# Sheet1.net
KiCad netlist of a schematic drawn in Altium Designer
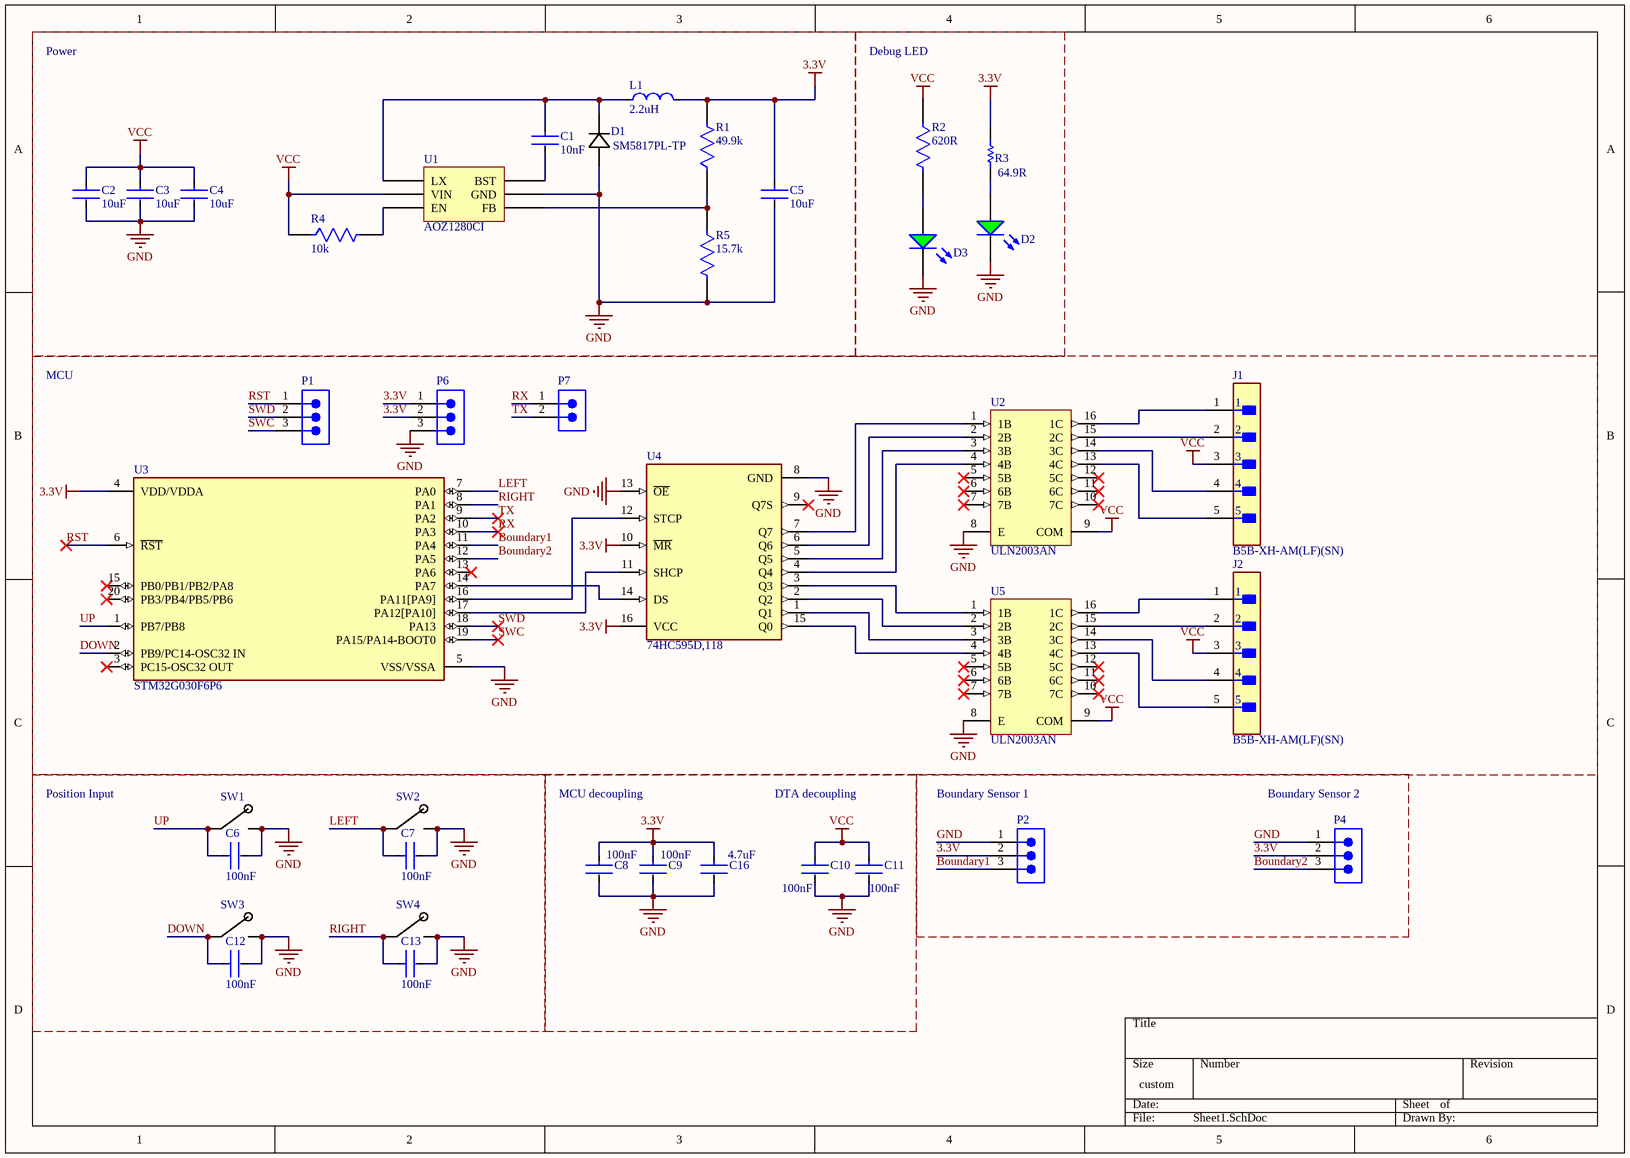
[diagram p0: Sheet1.SchDoc]

(export (version "E")
  (design (tool "Eeschema 10.0.6"))
  (components
    (comp (ref "C1")
      (value "10nF")
      (footprint "FP-CC0603-DA-MFG")
      (description "CAP CER 10000PF 50V X7R 0603")
      (fields (field (name "TOLERANCE") "0.1") (field (name "MANUFACTURER PART NUMBER") "CC0603KRX7R9BB103"))
      (libsource (lib "Altium Content Vault") (part "11868f565c42a9108669ba33697ecf6"))
    )
    (comp (ref "C2")
      (value "10uF")
      (footprint "FP-CL31-IPC_C")
      (description "CAP CER 10UF 50V X5R 1206")
      (fields (field (name "TOLERANCE") "10%") (field (name "MANUFACTURER") "Samsung"))
      (libsource (lib "Altium Content Vault") (part "11868f565c42a9108669ba33697ecf6"))
    )
    (comp (ref "C3")
      (value "10uF")
      (footprint "FP-CL31-IPC_C")
      (description "CAP CER 10UF 50V X5R 1206")
      (fields (field (name "TOLERANCE") "10%") (field (name "MANUFACTURER") "Samsung"))
      (libsource (lib "Altium Content Vault") (part "11868f565c42a9108669ba33697ecf6"))
    )
    (comp (ref "C4")
      (value "10uF")
      (footprint "FP-CL31-IPC_C")
      (description "CAP CER 10UF 50V X5R 1206")
      (fields (field (name "TOLERANCE") "10%") (field (name "MANUFACTURER") "Samsung"))
      (libsource (lib "Altium Content Vault") (part "11868f565c42a9108669ba33697ecf6"))
    )
    (comp (ref "C5")
      (value "10uF")
      (footprint "FP-CL10-IPC_C")
      (description "Cap Ceramic 10uF 6.3V X5R ±20% Pad SMD 0603 +85°C T/R")
      (fields (field (name "VOLTAGE") "6.3V") (field (name "TOLERANCE") "20%"))
      (libsource (lib "Altium Content Vault") (part "b4654b650e69147ec39a6b967a45e02"))
    )
    (comp (ref "C6")
      (value "100nF")
      (footprint "FP-CL10-0_1-MFG")
      (description "CAP CER 0.1UF 50V X7R 0603")
      (fields
        (field (name "MANUFACTURER") "Samsung Electro-Mechanics America, Inc")
        (field (name "MANUFACTURER PART NUMBER") "CL10B104JB8NNNC")
      )
      (libsource (lib "Altium Content Vault") (part "b4654b650e69147ec39a6b967a45e02"))
    )
    (comp (ref "C7")
      (value "100nF")
      (footprint "FP-CL10-0_1-MFG")
      (description "CAP CER 0.1UF 50V X7R 0603")
      (fields
        (field (name "MANUFACTURER") "Samsung Electro-Mechanics America, Inc")
        (field (name "MANUFACTURER PART NUMBER") "CL10B104JB8NNNC")
      )
      (libsource (lib "Altium Content Vault") (part "b4654b650e69147ec39a6b967a45e02"))
    )
    (comp (ref "C8")
      (value "100nF")
      (footprint "FP-CL10-0_1-MFG")
      (description "CAP CER 0.1UF 50V X7R 0603")
      (fields
        (field (name "MANUFACTURER") "Samsung Electro-Mechanics America, Inc")
        (field (name "MANUFACTURER PART NUMBER") "CL10B104JB8NNNC")
      )
      (libsource (lib "Altium Content Vault") (part "b4654b650e69147ec39a6b967a45e02"))
    )
    (comp (ref "C9")
      (value "100nF")
      (footprint "FP-CL10-0_1-MFG")
      (description "CAP CER 0.1UF 50V X7R 0603")
      (fields
        (field (name "MANUFACTURER") "Samsung Electro-Mechanics America, Inc")
        (field (name "MANUFACTURER PART NUMBER") "CL10B104JB8NNNC")
      )
      (libsource (lib "Altium Content Vault") (part "b4654b650e69147ec39a6b967a45e02"))
    )
    (comp (ref "C10")
      (value "100nF")
      (footprint "FP-CL10-0_1-MFG")
      (description "CAP CER 0.1UF 50V X7R 0603")
      (fields
        (field (name "MANUFACTURER") "Samsung Electro-Mechanics America, Inc")
        (field (name "MANUFACTURER PART NUMBER") "CL10B104JB8NNNC")
      )
      (libsource (lib "Altium Content Vault") (part "b4654b650e69147ec39a6b967a45e02"))
    )
    (comp (ref "C11")
      (value "100nF")
      (footprint "FP-CL10-0_1-MFG")
      (description "CAP CER 0.1UF 50V X7R 0603")
      (fields
        (field (name "MANUFACTURER") "Samsung Electro-Mechanics America, Inc")
        (field (name "MANUFACTURER PART NUMBER") "CL10B104JB8NNNC")
      )
      (libsource (lib "Altium Content Vault") (part "b4654b650e69147ec39a6b967a45e02"))
    )
    (comp (ref "C12")
      (value "100nF")
      (footprint "FP-CL10-0_1-MFG")
      (description "CAP CER 0.1UF 50V X7R 0603")
      (fields
        (field (name "MANUFACTURER") "Samsung Electro-Mechanics America, Inc")
        (field (name "MANUFACTURER PART NUMBER") "CL10B104JB8NNNC")
      )
      (libsource (lib "Altium Content Vault") (part "b4654b650e69147ec39a6b967a45e02"))
    )
    (comp (ref "C13")
      (value "100nF")
      (footprint "FP-CL10-0_1-MFG")
      (description "CAP CER 0.1UF 50V X7R 0603")
      (fields
        (field (name "MANUFACTURER") "Samsung Electro-Mechanics America, Inc")
        (field (name "MANUFACTURER PART NUMBER") "CL10B104JB8NNNC")
      )
      (libsource (lib "Altium Content Vault") (part "b4654b650e69147ec39a6b967a45e02"))
    )
    (comp (ref "C16")
      (value "CL10A475KP8NNNC")
      (footprint "FP-CL10-IPC_C")
      (description "Cap Ceramic 4.7uF 10V X5R ±10% Pad SMD 0603 +85°C T/R")
      (fields (field (name "CAPACITANCE") "4.7uF") (field (name "TOLERANCE") "10%"))
      (libsource (lib "Altium Content Vault") (part "b4654b650e69147ec39a6b967a45e02"))
    )
    (comp (ref "D1")
      (value "SM5817PL-TP")
      (footprint "SM5817PL-TP-Footprint-1")
      (description "DIODE SCHOTTKY 20V 1A SOD123FL")
      (libsource (lib "Bento") (part "SM5817PL-TP-Symbol-1"))
    )
    (comp (ref "D2")
      (value "150060VS75000")
      (footprint "WL-SMCW_0603_150060xx75000")
      (libsource (lib "Altium Content Vault") (part "LED_Green_2A-1K"))
    )
    (comp (ref "D3")
      (value "150060VS75000")
      (footprint "WL-SMCW_0603_150060xx75000")
      (libsource (lib "Altium Content Vault") (part "LED_Green_2A-1K"))
    )
    (comp (ref "J1")
      (value "B5B-XH-AM(LF)(SN)")
      (footprint "FP-B5B-XH-AM_LF_SN-MFG")
      (description "CONN HEADER VERT 5POS 2.5MM")
      (libsource (lib "Altium Content Vault") (part "bf93c07fd2649a848d0ec8585582aab"))
    )
    (comp (ref "J2")
      (value "B5B-XH-AM(LF)(SN)")
      (footprint "FP-B5B-XH-AM_LF_SN-MFG")
      (description "CONN HEADER VERT 5POS 2.5MM")
      (libsource (lib "Altium Content Vault") (part "bf93c07fd2649a848d0ec8585582aab"))
    )
    (comp (ref "L1")
      (value "2.2uH")
      (footprint "FP-LQM2MPN_G0-MFG")
      (description "Multilayer Type Inductor for Power Lines, 0806 (2016), 2.2μH, 30%, 0.138Ω, 1.2A")
      (fields (field (name "TOLERANCE") "30%"))
      (libsource (lib "Altium Content Vault") (part "725321dda6339637d4d059423bc1c3c"))
    )
    (comp (ref "P1")
      (value "61300311121")
      (footprint "61300311121")
      (libsource (lib "Altium Content Vault") (part "Header_Male_1R_03P"))
    )
    (comp (ref "P2")
      (value "61300311121")
      (footprint "61300311121")
      (libsource (lib "Altium Content Vault") (part "Header_Male_1R_03P"))
    )
    (comp (ref "P4")
      (value "61300311121")
      (footprint "61300311121")
      (libsource (lib "Altium Content Vault") (part "Header_Male_1R_03P"))
    )
    (comp (ref "P6")
      (value "61300311121")
      (footprint "61300311121")
      (libsource (lib "Altium Content Vault") (part "Header_Male_1R_03P"))
    )
    (comp (ref "P7")
      (value "61300211121")
      (footprint "61300211121")
      (libsource (lib "Altium Content Vault") (part "Header_Male_1R_02P"))
    )
    (comp (ref "R1")
      (value "49.9k")
      (footprint "FP-ERJ3EK-IPC_A")
      (description "RES SMD 49.9K OHM 1% 1/10W 0603")
      (fields (field (name "TOLERANCE") "1%"))
      (libsource (lib "Altium Content Vault") (part "1029c3af85768c4190bb7ad29bc67b5"))
    )
    (comp (ref "R2")
      (value "RMCF0603JT620R")
      (footprint "FP-RMCF0603-MFG")
      (description "620Ω ±5% 0.1W 0603 Thick Film Chip Resistor AEC-Q200 compliant")
      (fields (field (name "RESISTANCE") "620R") (field (name "TOLERANCE") "5%"))
      (libsource (lib "Altium Content Vault") (part "1029c3af85768c4190bb7ad29bc67b5"))
    )
    (comp (ref "R3")
      (value "64.9R")
      (footprint "RESC1608X55X25ML10T15")
      (description "RES 64.9 OHM 1% 1/10W 0603")
      (fields (field (name "MANUFACTURER") "Yageo") (field (name "PART NUMBER") "RC0603FR-0764R9L"))
      (libsource (lib "Altium Content Vault") (part "RES"))
    )
    (comp (ref "R4")
      (value "10k")
      (footprint "FP-RMCF0603-IPC_C")
      (description "10kΩ ±5% 0.1W 0603 Thick Film Chip Resistor AEC-Q200 compliant")
      (fields (field (name "TOLERANCE") "5%"))
      (libsource (lib "Altium Content Vault") (part "1029c3af85768c4190bb7ad29bc67b5"))
    )
    (comp (ref "R5")
      (value "15.7k")
      (footprint "FP-RT0603-MFG")
      (description "RES SMD 15.8K OHM 0.1% 1/10W")
      (fields
        (field (name "OCTOPART") "https://octopart.com/rt0603brd0715k8l-yageo-1418310")
        (field (name "TOLERANCE") "0.001")
      )
      (libsource (lib "Altium Content Vault") (part "1029c3af85768c4190bb7ad29bc67b5"))
    )
    (comp (ref "SW1")
      (value "PTS636 SM43 SMTR LFS")
      (footprint "PTS636 SM43 SMTR LFS-Footprint-1")
      (description "SWITCH TACTILE SPST-NO 0.05A 12V")
      (libsource (lib "Bento") (part "PTS636 SM43 SMTR LFS-Symbol-1"))
    )
    (comp (ref "SW2")
      (value "PTS636 SM43 SMTR LFS")
      (footprint "PTS636 SM43 SMTR LFS-Footprint-1")
      (description "SWITCH TACTILE SPST-NO 0.05A 12V")
      (libsource (lib "Bento") (part "PTS636 SM43 SMTR LFS-Symbol-1"))
    )
    (comp (ref "SW3")
      (value "PTS636 SM43 SMTR LFS")
      (footprint "PTS636 SM43 SMTR LFS-Footprint-1")
      (description "SWITCH TACTILE SPST-NO 0.05A 12V")
      (libsource (lib "Bento") (part "PTS636 SM43 SMTR LFS-Symbol-1"))
    )
    (comp (ref "SW4")
      (value "PTS636 SM43 SMTR LFS")
      (footprint "PTS636 SM43 SMTR LFS-Footprint-1")
      (description "SWITCH TACTILE SPST-NO 0.05A 12V")
      (libsource (lib "Bento") (part "PTS636 SM43 SMTR LFS-Symbol-1"))
    )
    (comp (ref "U1")
      (value "AOZ1280CI")
      (footprint "SOT95P280X125-6N")
      (description "Buck Switching Regulator IC Positive Adjustable 0.8V 1 Output 1.2A SOT-23-6")
      (libsource (lib "Bento") (part "AOZ1280CI-Symbol-1"))
    )
    (comp (ref "U2")
      (value "ULN2003AN")
      (footprint "N0016A")
      (fields (field (name "MANUFACTURER") "TexasInstruments"))
      (libsource (lib "Altium Content Vault") (part "TI-ULN2003A-PDIP_N-16"))
    )
    (comp (ref "U3")
      (value "STM32G030F6P6")
      (footprint "FP-TSSOP20-YA-MFG")
      (description "ARM MICROCONTROLLERS - MCU")
      (fields
        (field (name "MANUFACTURER") "STMicroelectronics")
        (field (name "OCTOPART") "https://octopart.com/stm32g030f6p6-stmicroelectronics-103773023")
      )
      (libsource (lib "Altium Content Vault") (part "de2f7cf56ecdc1f1ec6ab3e49dbf5e6"))
    )
    (comp (ref "U4")
      (value "74HC595D,118")
      (footprint "FP-SOT109-1-IPC_C")
      (description "IC SHIFT REGISTER 8BIT 16SOIC")
      (libsource (lib "Altium Content Vault") (part "7b153f231cfcc3ac06dee253bd56617"))
    )
    (comp (ref "U5")
      (value "ULN2003AN")
      (footprint "N0016A")
      (fields (field (name "MANUFACTURER") "TexasInstruments"))
      (libsource (lib "Altium Content Vault") (part "TI-ULN2003A-PDIP_N-16"))
    )
  )
  (nets
    (net (code "1") (name "/Boundary1") (class "Default")
      (node (ref "P2") (pin "3") (pinfunction "3_3") (pintype "passive"))
      (node (ref "U3") (pin "11") (pinfunction "PA4_11") (pintype "bidirectional"))
    )
    (net (code "2") (name "/Boundary2") (class "Default")
      (node (ref "P4") (pin "3") (pinfunction "3_3") (pintype "passive"))
      (node (ref "U3") (pin "12") (pinfunction "PA5_12") (pintype "bidirectional"))
    )
    (net (code "3") (name "/DOWN") (class "Default")
      (node (ref "C12") (pin "1") (pinfunction "1_1") (pintype "passive"))
      (node (ref "SW3") (pin "1") (pinfunction "1_1") (pintype "passive"))
      (node (ref "U3") (pin "2") (pinfunction "PB9/PC14-OSC32_IN_2") (pintype "bidirectional"))
    )
    (net (code "4") (name "/LEFT") (class "Default")
      (node (ref "C7") (pin "1") (pinfunction "1_1") (pintype "passive"))
      (node (ref "SW2") (pin "1") (pinfunction "1_1") (pintype "passive"))
      (node (ref "U3") (pin "7") (pinfunction "PA0_7") (pintype "bidirectional"))
    )
    (net (code "5") (name "/RIGHT") (class "Default")
      (node (ref "C13") (pin "1") (pinfunction "1_1") (pintype "passive"))
      (node (ref "SW4") (pin "1") (pinfunction "1_1") (pintype "passive"))
      (node (ref "U3") (pin "8") (pinfunction "PA1_8") (pintype "bidirectional"))
    )
    (net (code "6") (name "/RST") (class "Default")
      (node (ref "P1") (pin "1") (pinfunction "1_1") (pintype "passive"))
      (node (ref "U3") (pin "6") (pinfunction "~{RST}_6") (pintype "input"))
    )
    (net (code "7") (name "/RX") (class "Default")
      (node (ref "P7") (pin "1") (pinfunction "1_1") (pintype "passive"))
      (node (ref "U3") (pin "10") (pinfunction "PA3_10") (pintype "bidirectional"))
    )
    (net (code "8") (name "/SWC") (class "Default")
      (node (ref "P1") (pin "3") (pinfunction "3_3") (pintype "passive"))
      (node (ref "U3") (pin "19") (pinfunction "PA15/PA14-BOOT0_19") (pintype "bidirectional"))
    )
    (net (code "9") (name "/SWD") (class "Default")
      (node (ref "P1") (pin "2") (pinfunction "2_2") (pintype "passive"))
      (node (ref "U3") (pin "18") (pinfunction "PA13_18") (pintype "bidirectional"))
    )
    (net (code "10") (name "/TX") (class "Default")
      (node (ref "P7") (pin "2") (pinfunction "2_2") (pintype "passive"))
      (node (ref "U3") (pin "9") (pinfunction "PA2_9") (pintype "bidirectional"))
    )
    (net (code "11") (name "/UP") (class "Default")
      (node (ref "C6") (pin "1") (pinfunction "1_1") (pintype "passive"))
      (node (ref "SW1") (pin "1") (pinfunction "1_1") (pintype "passive"))
      (node (ref "U3") (pin "1") (pinfunction "PB7/PB8_1") (pintype "bidirectional"))
    )
    (net (code "12") (name "3.3V") (class "Default")
      (node (ref "C16") (pin "1") (pinfunction "1_1") (pintype "passive"))
      (node (ref "C5") (pin "1") (pinfunction "1_1") (pintype "passive"))
      (node (ref "C8") (pin "1") (pinfunction "1_1") (pintype "passive"))
      (node (ref "C9") (pin "1") (pinfunction "1_1") (pintype "passive"))
      (node (ref "L1") (pin "2") (pinfunction "2_2") (pintype "passive"))
      (node (ref "P2") (pin "2") (pinfunction "2_2") (pintype "passive"))
      (node (ref "P4") (pin "2") (pinfunction "2_2") (pintype "passive"))
      (node (ref "P6") (pin "1") (pinfunction "1_1") (pintype "passive"))
      (node (ref "P6") (pin "2") (pinfunction "2_2") (pintype "passive"))
      (node (ref "R1") (pin "2") (pinfunction "2_2") (pintype "passive"))
      (node (ref "R3") (pin "2") (pinfunction "2_2") (pintype "passive"))
      (node (ref "U3") (pin "4") (pinfunction "VDD/VDDA_4") (pintype "power_in"))
      (node (ref "U4") (pin "10") (pinfunction "~{MR}_10") (pintype "input"))
      (node (ref "U4") (pin "16") (pinfunction "VCC_16") (pintype "power_in"))
    )
    (net (code "13") (name "GND") (class "Default")
      (node (ref "C10") (pin "2") (pinfunction "2_2") (pintype "passive"))
      (node (ref "C11") (pin "2") (pinfunction "2_2") (pintype "passive"))
      (node (ref "C12") (pin "2") (pinfunction "2_2") (pintype "passive"))
      (node (ref "C13") (pin "2") (pinfunction "2_2") (pintype "passive"))
      (node (ref "C16") (pin "2") (pinfunction "2_2") (pintype "passive"))
      (node (ref "C2") (pin "2") (pinfunction "2_2") (pintype "passive"))
      (node (ref "C3") (pin "2") (pinfunction "2_2") (pintype "passive"))
      (node (ref "C4") (pin "2") (pinfunction "2_2") (pintype "passive"))
      (node (ref "C5") (pin "2") (pinfunction "2_2") (pintype "passive"))
      (node (ref "C6") (pin "2") (pinfunction "2_2") (pintype "passive"))
      (node (ref "C7") (pin "2") (pinfunction "2_2") (pintype "passive"))
      (node (ref "C8") (pin "2") (pinfunction "2_2") (pintype "passive"))
      (node (ref "C9") (pin "2") (pinfunction "2_2") (pintype "passive"))
      (node (ref "D1") (pin "2") (pinfunction "2_2") (pintype "passive"))
      (node (ref "D2") (pin "1") (pinfunction "K_1") (pintype "passive"))
      (node (ref "D3") (pin "1") (pinfunction "K_1") (pintype "passive"))
      (node (ref "P2") (pin "1") (pinfunction "1_1") (pintype "passive"))
      (node (ref "P4") (pin "1") (pinfunction "1_1") (pintype "passive"))
      (node (ref "P6") (pin "3") (pinfunction "3_3") (pintype "passive"))
      (node (ref "R5") (pin "2") (pinfunction "2_2") (pintype "passive"))
      (node (ref "SW1") (pin "2") (pinfunction "2_2") (pintype "passive"))
      (node (ref "SW2") (pin "2") (pinfunction "2_2") (pintype "passive"))
      (node (ref "SW3") (pin "2") (pinfunction "2_2") (pintype "passive"))
      (node (ref "SW4") (pin "2") (pinfunction "2_2") (pintype "passive"))
      (node (ref "U1") (pin "2") (pinfunction "GND_2") (pintype "passive"))
      (node (ref "U2") (pin "8") (pinfunction "E_8") (pintype "passive"))
      (node (ref "U3") (pin "5") (pinfunction "VSS/VSSA_5") (pintype "power_in"))
      (node (ref "U4") (pin "13") (pinfunction "~{OE}_13") (pintype "input"))
      (node (ref "U4") (pin "8") (pinfunction "GND_8") (pintype "power_in"))
      (node (ref "U5") (pin "8") (pinfunction "E_8") (pintype "passive"))
    )
    (net (code "14") (name "Net-(D2-A)") (class "Default")
      (node (ref "D2") (pin "2") (pinfunction "A_2") (pintype "passive"))
      (node (ref "R3") (pin "1") (pinfunction "1_1") (pintype "passive"))
    )
    (net (code "15") (name "Net-(D3-A)") (class "Default")
      (node (ref "D3") (pin "2") (pinfunction "A_2") (pintype "passive"))
      (node (ref "R2") (pin "2") (pinfunction "2_2") (pintype "passive"))
    )
    (net (code "16") (name "Net-(U1-BST)") (class "Default")
      (node (ref "C1") (pin "2") (pinfunction "2_2") (pintype "passive"))
      (node (ref "U1") (pin "1") (pinfunction "BST_1") (pintype "passive"))
    )
    (net (code "17") (name "Net-(U1-EN)") (class "Default")
      (node (ref "R4") (pin "2") (pinfunction "2_2") (pintype "passive"))
      (node (ref "U1") (pin "4") (pinfunction "EN_4") (pintype "passive"))
    )
    (net (code "18") (name "Net-(U1-FB)") (class "Default")
      (node (ref "R1") (pin "1") (pinfunction "1_1") (pintype "passive"))
      (node (ref "R5") (pin "1") (pinfunction "1_1") (pintype "passive"))
      (node (ref "U1") (pin "3") (pinfunction "FB_3") (pintype "passive"))
    )
    (net (code "19") (name "Net-(U1-LX)") (class "Default")
      (node (ref "C1") (pin "1") (pinfunction "1_1") (pintype "passive"))
      (node (ref "D1") (pin "1") (pinfunction "1_1") (pintype "passive"))
      (node (ref "L1") (pin "1") (pinfunction "1_1") (pintype "passive"))
      (node (ref "U1") (pin "6") (pinfunction "LX_6") (pintype "passive"))
    )
    (net (code "20") (name "Net-(U2-1B)") (class "Default")
      (node (ref "U2") (pin "1") (pinfunction "1B_1") (pintype "input"))
      (node (ref "U4") (pin "7") (pinfunction "Q7_7") (pintype "output"))
    )
    (net (code "21") (name "Net-(U2-1C)") (class "Default")
      (node (ref "J1") (pin "1") (pinfunction "1_1") (pintype "passive"))
      (node (ref "U2") (pin "16") (pinfunction "1C_16") (pintype "output"))
    )
    (net (code "22") (name "Net-(U2-2B)") (class "Default")
      (node (ref "U2") (pin "2") (pinfunction "2B_2") (pintype "input"))
      (node (ref "U4") (pin "6") (pinfunction "Q6_6") (pintype "output"))
    )
    (net (code "23") (name "Net-(U2-2C)") (class "Default")
      (node (ref "J1") (pin "2") (pinfunction "2_2") (pintype "passive"))
      (node (ref "U2") (pin "15") (pinfunction "2C_15") (pintype "output"))
    )
    (net (code "24") (name "Net-(U2-3B)") (class "Default")
      (node (ref "U2") (pin "3") (pinfunction "3B_3") (pintype "input"))
      (node (ref "U4") (pin "5") (pinfunction "Q5_5") (pintype "output"))
    )
    (net (code "25") (name "Net-(U2-3C)") (class "Default")
      (node (ref "J1") (pin "4") (pinfunction "4_4") (pintype "passive"))
      (node (ref "U2") (pin "14") (pinfunction "3C_14") (pintype "output"))
    )
    (net (code "26") (name "Net-(U2-4B)") (class "Default")
      (node (ref "U2") (pin "4") (pinfunction "4B_4") (pintype "input"))
      (node (ref "U4") (pin "4") (pinfunction "Q4_4") (pintype "output"))
    )
    (net (code "27") (name "Net-(U2-4C)") (class "Default")
      (node (ref "J1") (pin "5") (pinfunction "5_5") (pintype "passive"))
      (node (ref "U2") (pin "13") (pinfunction "4C_13") (pintype "output"))
    )
    (net (code "28") (name "Net-(U3-PA7)") (class "Default")
      (node (ref "U3") (pin "14") (pinfunction "PA7_14") (pintype "bidirectional"))
      (node (ref "U4") (pin "14") (pinfunction "DS_14") (pintype "input"))
    )
    (net (code "29") (name "Net-(U3-PA11[PA9])") (class "Default")
      (node (ref "U3") (pin "16") (pinfunction "PA11[PA9]_16") (pintype "bidirectional"))
      (node (ref "U4") (pin "12") (pinfunction "STCP_12") (pintype "input"))
    )
    (net (code "30") (name "Net-(U3-PA12[PA10])") (class "Default")
      (node (ref "U3") (pin "17") (pinfunction "PA12[PA10]_17") (pintype "bidirectional"))
      (node (ref "U4") (pin "11") (pinfunction "SHCP_11") (pintype "input"))
    )
    (net (code "31") (name "Net-(U4-Q0)") (class "Default")
      (node (ref "U4") (pin "15") (pinfunction "Q0_15") (pintype "output"))
      (node (ref "U5") (pin "4") (pinfunction "4B_4") (pintype "input"))
    )
    (net (code "32") (name "Net-(U4-Q1)") (class "Default")
      (node (ref "U4") (pin "1") (pinfunction "Q1_1") (pintype "output"))
      (node (ref "U5") (pin "3") (pinfunction "3B_3") (pintype "input"))
    )
    (net (code "33") (name "Net-(U4-Q2)") (class "Default")
      (node (ref "U4") (pin "2") (pinfunction "Q2_2") (pintype "output"))
      (node (ref "U5") (pin "2") (pinfunction "2B_2") (pintype "input"))
    )
    (net (code "34") (name "Net-(U4-Q3)") (class "Default")
      (node (ref "U4") (pin "3") (pinfunction "Q3_3") (pintype "output"))
      (node (ref "U5") (pin "1") (pinfunction "1B_1") (pintype "input"))
    )
    (net (code "35") (name "Net-(U5-1C)") (class "Default")
      (node (ref "J2") (pin "1") (pinfunction "1_1") (pintype "passive"))
      (node (ref "U5") (pin "16") (pinfunction "1C_16") (pintype "output"))
    )
    (net (code "36") (name "Net-(U5-2C)") (class "Default")
      (node (ref "J2") (pin "2") (pinfunction "2_2") (pintype "passive"))
      (node (ref "U5") (pin "15") (pinfunction "2C_15") (pintype "output"))
    )
    (net (code "37") (name "Net-(U5-3C)") (class "Default")
      (node (ref "J2") (pin "4") (pinfunction "4_4") (pintype "passive"))
      (node (ref "U5") (pin "14") (pinfunction "3C_14") (pintype "output"))
    )
    (net (code "38") (name "Net-(U5-4C)") (class "Default")
      (node (ref "J2") (pin "5") (pinfunction "5_5") (pintype "passive"))
      (node (ref "U5") (pin "13") (pinfunction "4C_13") (pintype "output"))
    )
    (net (code "39") (name "VCC") (class "Default")
      (node (ref "C10") (pin "1") (pinfunction "1_1") (pintype "passive"))
      (node (ref "C11") (pin "1") (pinfunction "1_1") (pintype "passive"))
      (node (ref "C2") (pin "1") (pinfunction "1_1") (pintype "passive"))
      (node (ref "C3") (pin "1") (pinfunction "1_1") (pintype "passive"))
      (node (ref "C4") (pin "1") (pinfunction "1_1") (pintype "passive"))
      (node (ref "J1") (pin "3") (pinfunction "3_3") (pintype "passive"))
      (node (ref "J2") (pin "3") (pinfunction "3_3") (pintype "passive"))
      (node (ref "R2") (pin "1") (pinfunction "1_1") (pintype "passive"))
      (node (ref "R4") (pin "1") (pinfunction "1_1") (pintype "passive"))
      (node (ref "U1") (pin "5") (pinfunction "VIN_5") (pintype "power_in"))
      (node (ref "U2") (pin "9") (pinfunction "COM_9") (pintype "passive"))
      (node (ref "U5") (pin "9") (pinfunction "COM_9") (pintype "passive"))
    )
    (net (code "40") (name "unconnected-(U2-5B-Pad5)") (class "Default")
      (node (ref "U2") (pin "5") (pinfunction "5B_5") (pintype "input+no_connect"))
    )
    (net (code "41") (name "unconnected-(U2-5C-Pad12)") (class "Default")
      (node (ref "U2") (pin "12") (pinfunction "5C_12") (pintype "output+no_connect"))
    )
    (net (code "42") (name "unconnected-(U2-6B-Pad6)") (class "Default")
      (node (ref "U2") (pin "6") (pinfunction "6B_6") (pintype "input+no_connect"))
    )
    (net (code "43") (name "unconnected-(U2-6C-Pad11)") (class "Default")
      (node (ref "U2") (pin "11") (pinfunction "6C_11") (pintype "output+no_connect"))
    )
    (net (code "44") (name "unconnected-(U2-7B-Pad7)") (class "Default")
      (node (ref "U2") (pin "7") (pinfunction "7B_7") (pintype "input+no_connect"))
    )
    (net (code "45") (name "unconnected-(U2-7C-Pad10)") (class "Default")
      (node (ref "U2") (pin "10") (pinfunction "7C_10") (pintype "output+no_connect"))
    )
    (net (code "46") (name "unconnected-(U3-PA6-Pad13)") (class "Default")
      (node (ref "U3") (pin "13") (pinfunction "PA6_13") (pintype "bidirectional+no_connect"))
    )
    (net (code "47") (name "unconnected-(U3-PB0{slash}PB1{slash}PB2{slash}PA8-Pad15)") (class "Default")
      (node (ref "U3") (pin "15") (pinfunction "PB0/PB1/PB2/PA8_15") (pintype "bidirectional+no_connect"))
    )
    (net (code "48") (name "unconnected-(U3-PB3{slash}PB4{slash}PB5{slash}PB6-Pad20)") (class "Default")
      (node (ref "U3") (pin "20") (pinfunction "PB3/PB4/PB5/PB6_20") (pintype "bidirectional+no_connect"))
    )
    (net (code "49") (name "unconnected-(U3-PC15-OSC32_OUT-Pad3)") (class "Default")
      (node (ref "U3") (pin "3") (pinfunction "PC15-OSC32_OUT_3") (pintype "bidirectional+no_connect"))
    )
    (net (code "50") (name "unconnected-(U4-Q7S-Pad9)") (class "Default")
      (node (ref "U4") (pin "9") (pinfunction "Q7S_9") (pintype "output+no_connect"))
    )
    (net (code "51") (name "unconnected-(U5-5B-Pad5)") (class "Default")
      (node (ref "U5") (pin "5") (pinfunction "5B_5") (pintype "input+no_connect"))
    )
    (net (code "52") (name "unconnected-(U5-5C-Pad12)") (class "Default")
      (node (ref "U5") (pin "12") (pinfunction "5C_12") (pintype "output+no_connect"))
    )
    (net (code "53") (name "unconnected-(U5-6B-Pad6)") (class "Default")
      (node (ref "U5") (pin "6") (pinfunction "6B_6") (pintype "input+no_connect"))
    )
    (net (code "54") (name "unconnected-(U5-6C-Pad11)") (class "Default")
      (node (ref "U5") (pin "11") (pinfunction "6C_11") (pintype "output+no_connect"))
    )
    (net (code "55") (name "unconnected-(U5-7B-Pad7)") (class "Default")
      (node (ref "U5") (pin "7") (pinfunction "7B_7") (pintype "input+no_connect"))
    )
    (net (code "56") (name "unconnected-(U5-7C-Pad10)") (class "Default")
      (node (ref "U5") (pin "10") (pinfunction "7C_10") (pintype "output+no_connect"))
    )
  )
)
